# USB3-HUB.net
KiCad netlist of a schematic drawn in Altium Designer
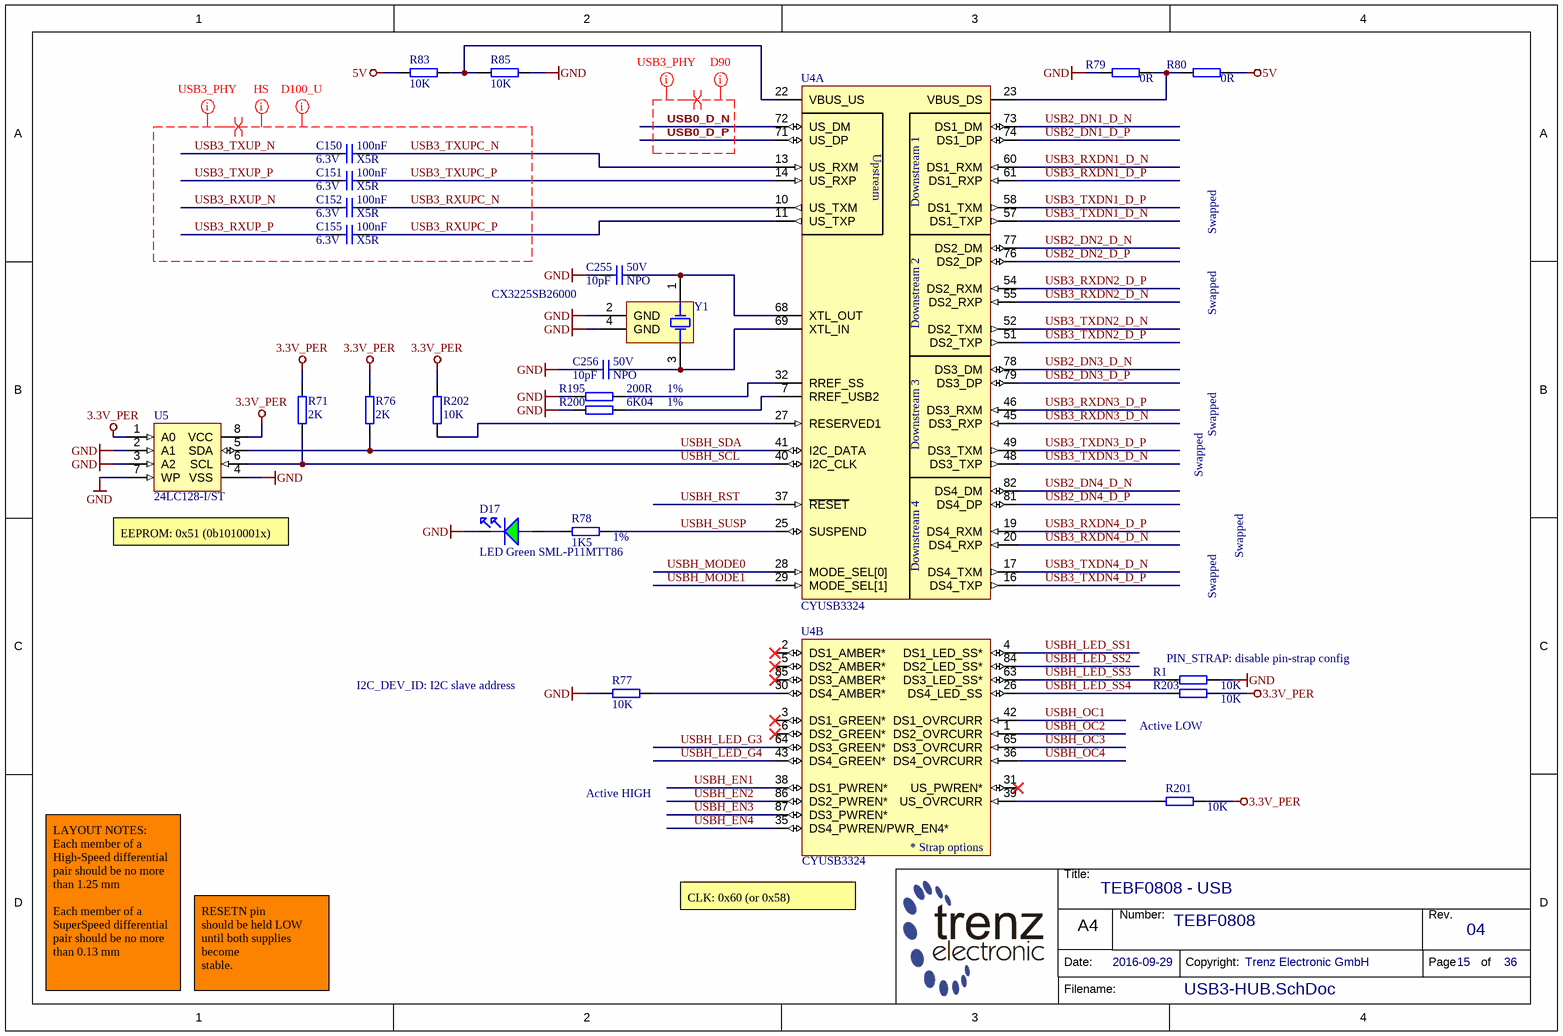
[diagram p0: USB3-HUB.SchDoc]

(export (version "E")
  (design (tool "Eeschema 10.0.6"))
  (components
    (comp (ref "C150")
      (value "100nF")
      (footprint "CAPC0603X33N")
      (description "KON 100nF 6.3V X5R SMD 10%")
      (fields
        (field (name "VOLTAGE") "6.3V")
        (field (name "TECHNOLOGY") "X5R")
        (field (name "TOLERANCE") "10%")
      )
      (libsource (lib "TE") (part "CAP-NP"))
    )
    (comp (ref "C151")
      (value "100nF")
      (footprint "CAPC0603X33N")
      (description "KON 100nF 6.3V X5R SMD 10%")
      (fields
        (field (name "VOLTAGE") "6.3V")
        (field (name "TECHNOLOGY") "X5R")
        (field (name "TOLERANCE") "10%")
      )
      (libsource (lib "TE") (part "CAP-NP"))
    )
    (comp (ref "C152")
      (value "100nF")
      (footprint "CAPC0603X33N")
      (description "KON 100nF 6.3V X5R SMD 10%")
      (fields
        (field (name "VOLTAGE") "6.3V")
        (field (name "TECHNOLOGY") "X5R")
        (field (name "TOLERANCE") "10%")
      )
      (libsource (lib "TE") (part "CAP-NP"))
    )
    (comp (ref "C155")
      (value "100nF")
      (footprint "CAPC0603X33N")
      (description "KON 100nF 6.3V X5R SMD 10%")
      (fields
        (field (name "VOLTAGE") "6.3V")
        (field (name "TECHNOLOGY") "X5R")
        (field (name "TOLERANCE") "10%")
      )
      (libsource (lib "TE") (part "CAP-NP"))
    )
    (comp (ref "C255")
      (value "10pF")
      (footprint "CAPC1005X55N")
      (description "KON 10pF NPO 50V SMD 5%")
      (fields
        (field (name "VOLTAGE") "50V")
        (field (name "TECHNOLOGY") "NPO")
        (field (name "TOLERANCE") "5%")
      )
      (libsource (lib "TE") (part "CAP-NP"))
    )
    (comp (ref "C256")
      (value "10pF")
      (footprint "CAPC1005X55N")
      (description "KON 10pF NPO 50V SMD 5%")
      (fields
        (field (name "VOLTAGE") "50V")
        (field (name "TECHNOLOGY") "NPO")
        (field (name "TOLERANCE") "5%")
      )
      (libsource (lib "TE") (part "CAP-NP"))
    )
    (comp (ref "D17")
      (value "LED Green SML-P11MTT86")
      (footprint "LEDC1006X25N_GREEN")
      (description "LED Grün SML-P11MTT86 SMD")
      (libsource (lib "TE") (part "LED_GRUEN"))
    )
    (comp (ref "R1")
      (value "10K")
      (footprint "RESC1005X40N")
      (description "WID SMD 10K 1% 0,063W")
      (fields (field (name "TOLERANCE") "1%"))
      (libsource (lib "TE") (part "RES"))
    )
    (comp (ref "R71")
      (value "2K")
      (footprint "RESC1005X40N")
      (description "WID SMD 2K 1% 0,063W")
      (fields (field (name "TOLERANCE") "1%"))
      (libsource (lib "TE") (part "RES"))
    )
    (comp (ref "R76")
      (value "2K")
      (footprint "RESC1005X40N")
      (description "WID SMD 2K 1% 0,063W")
      (fields (field (name "TOLERANCE") "1%"))
      (libsource (lib "TE") (part "RES"))
    )
    (comp (ref "R77")
      (value "10K")
      (footprint "RESC1005X40N")
      (description "WID SMD 10K 1% 0,063W")
      (fields (field (name "TOLERANCE") "1%"))
      (libsource (lib "TE") (part "RES"))
    )
    (comp (ref "R78")
      (value "1K5")
      (footprint "RESC1005X40N")
      (description "WID SMD 1K5 1% 0,063W")
      (fields (field (name "TOLERANCE") "1%"))
      (libsource (lib "TE") (part "RES"))
    )
    (comp (ref "R79")
      (value "0R")
      (footprint "RESC1005X40N")
      (description "WID SMD 0R")
      (fields (field (name "TOLERANCE") "1%"))
      (libsource (lib "TE") (part "RES"))
    )
    (comp (ref "R80")
      (value "0R")
      (footprint "RESC1005X40N")
      (description "WID SMD 0R")
      (fields (field (name "TOLERANCE") "1%"))
      (libsource (lib "TE") (part "RES"))
    )
    (comp (ref "R83")
      (value "10K")
      (footprint "RESC1005X40N")
      (description "WID SMD 10K 1% 0,063W")
      (fields (field (name "TOLERANCE") "1%"))
      (libsource (lib "TE") (part "RES"))
    )
    (comp (ref "R85")
      (value "10K")
      (footprint "RESC1005X40N")
      (description "WID SMD 10K 1% 0,063W")
      (fields (field (name "TOLERANCE") "1%"))
      (libsource (lib "TE") (part "RES"))
    )
    (comp (ref "R195")
      (value "200R")
      (footprint "RESC1005X40N")
      (description "WID SMD 200R 1% 0,063W")
      (fields (field (name "TOLERANCE") "1%"))
      (libsource (lib "TE") (part "RES"))
    )
    (comp (ref "R200")
      (value "6K04")
      (footprint "RESC1005X40N")
      (description "WID SMD 6K04 1% 0,063W")
      (fields (field (name "TOLERANCE") "1%"))
      (libsource (lib "TE") (part "RES"))
    )
    (comp (ref "R201")
      (value "10K")
      (footprint "RESC1005X40N")
      (description "WID SMD 10K 1% 0,063W")
      (fields (field (name "TOLERANCE") "1%"))
      (libsource (lib "TE") (part "RES"))
    )
    (comp (ref "R202")
      (value "10K")
      (footprint "RESC1005X40N")
      (description "WID SMD 10K 1% 0,063W")
      (fields (field (name "TOLERANCE") "1%"))
      (libsource (lib "TE") (part "RES"))
    )
    (comp (ref "R203")
      (value "10K")
      (footprint "RESC1005X40N")
      (description "WID SMD 10K 1% 0,063W")
      (fields (field (name "TOLERANCE") "1%"))
      (libsource (lib "TE") (part "RES"))
    )
    (comp (ref "U4")
      (value "CYUSB3324")
      (footprint "QFN40P10X10X1-89T530")
      (description "CYUSB3324-88LTXC USB 3.0 Hub")
      (libsource (lib "TE") (part "CYUSB3324"))
    )
    (comp (ref "U5")
      (value "24LC128-I/ST")
      (footprint "SOP65P640X120-8N-MC")
      (libsource (lib "TE") (part "24LC128I"))
    )
    (comp (ref "Y1")
      (value "CX3225SB26000")
      (footprint "OSCCC320X250X60N")
      (description "Quarz Crystal 26Mhz 10ppm 8pF -20C +70°C")
      (libsource (lib "TE") (part "ABM8G"))
    )
  )
  (nets
    (net (code "1") (name "/USB0_D_N") (class "Default")
      (node (ref "U4") (pin "72") (pinfunction "US_DM_72") (pintype "bidirectional"))
    )
    (net (code "2") (name "/USB0_D_P") (class "Default")
      (node (ref "U4") (pin "71") (pinfunction "US_DP_71") (pintype "bidirectional"))
    )
    (net (code "3") (name "/USB2_DN1_D_N") (class "Default")
      (node (ref "U4") (pin "73") (pinfunction "DS1_DM_73") (pintype "bidirectional"))
    )
    (net (code "4") (name "/USB2_DN1_D_P") (class "Default")
      (node (ref "U4") (pin "74") (pinfunction "DS1_DP_74") (pintype "bidirectional"))
    )
    (net (code "5") (name "/USB2_DN2_D_N") (class "Default")
      (node (ref "U4") (pin "77") (pinfunction "DS2_DM_77") (pintype "bidirectional"))
    )
    (net (code "6") (name "/USB2_DN2_D_P") (class "Default")
      (node (ref "U4") (pin "76") (pinfunction "DS2_DP_76") (pintype "bidirectional"))
    )
    (net (code "7") (name "/USB2_DN3_D_N") (class "Default")
      (node (ref "U4") (pin "78") (pinfunction "DS3_DM_78") (pintype "bidirectional"))
    )
    (net (code "8") (name "/USB2_DN3_D_P") (class "Default")
      (node (ref "U4") (pin "79") (pinfunction "DS3_DP_79") (pintype "bidirectional"))
    )
    (net (code "9") (name "/USB2_DN4_D_N") (class "Default")
      (node (ref "U4") (pin "82") (pinfunction "DS4_DM_82") (pintype "bidirectional"))
    )
    (net (code "10") (name "/USB2_DN4_D_P") (class "Default")
      (node (ref "U4") (pin "81") (pinfunction "DS4_DP_81") (pintype "bidirectional"))
    )
    (net (code "11") (name "/USB3_RXDN1_D_N") (class "Default")
      (node (ref "U4") (pin "60") (pinfunction "DS1_RXM_60") (pintype "input"))
    )
    (net (code "12") (name "/USB3_RXDN1_D_P") (class "Default")
      (node (ref "U4") (pin "61") (pinfunction "DS1_RXP_61") (pintype "input"))
    )
    (net (code "13") (name "/USB3_RXDN2_D_N") (class "Default")
      (node (ref "U4") (pin "55") (pinfunction "DS2_RXP_55") (pintype "input"))
    )
    (net (code "14") (name "/USB3_RXDN2_D_P") (class "Default")
      (node (ref "U4") (pin "54") (pinfunction "DS2_RXM_54") (pintype "input"))
    )
    (net (code "15") (name "/USB3_RXDN3_D_N") (class "Default")
      (node (ref "U4") (pin "45") (pinfunction "DS3_RXP_45") (pintype "input"))
    )
    (net (code "16") (name "/USB3_RXDN3_D_P") (class "Default")
      (node (ref "U4") (pin "46") (pinfunction "DS3_RXM_46") (pintype "input"))
    )
    (net (code "17") (name "/USB3_RXDN4_D_N") (class "Default")
      (node (ref "U4") (pin "20") (pinfunction "DS4_RXP_20") (pintype "input"))
    )
    (net (code "18") (name "/USB3_RXDN4_D_P") (class "Default")
      (node (ref "U4") (pin "19") (pinfunction "DS4_RXM_19") (pintype "input"))
    )
    (net (code "19") (name "/USB3_RXUPC_N") (class "Default")
      (node (ref "C152") (pin "2") (pinfunction "2_2") (pintype "passive"))
      (node (ref "U4") (pin "10") (pinfunction "US_TXM_10") (pintype "output"))
    )
    (net (code "20") (name "/USB3_RXUPC_P") (class "Default")
      (node (ref "C155") (pin "2") (pinfunction "2_2") (pintype "passive"))
      (node (ref "U4") (pin "11") (pinfunction "US_TXP_11") (pintype "output"))
    )
    (net (code "21") (name "/USB3_RXUP_N") (class "Default")
      (node (ref "C152") (pin "1") (pinfunction "1_1") (pintype "passive"))
    )
    (net (code "22") (name "/USB3_RXUP_P") (class "Default")
      (node (ref "C155") (pin "1") (pinfunction "1_1") (pintype "passive"))
    )
    (net (code "23") (name "/USB3_TXDN1_D_N") (class "Default")
      (node (ref "U4") (pin "57") (pinfunction "DS1_TXP_57") (pintype "output"))
    )
    (net (code "24") (name "/USB3_TXDN1_D_P") (class "Default")
      (node (ref "U4") (pin "58") (pinfunction "DS1_TXM_58") (pintype "output"))
    )
    (net (code "25") (name "/USB3_TXDN2_D_N") (class "Default")
      (node (ref "U4") (pin "52") (pinfunction "DS2_TXM_52") (pintype "output"))
    )
    (net (code "26") (name "/USB3_TXDN2_D_P") (class "Default")
      (node (ref "U4") (pin "51") (pinfunction "DS2_TXP_51") (pintype "output"))
    )
    (net (code "27") (name "/USB3_TXDN3_D_N") (class "Default")
      (node (ref "U4") (pin "48") (pinfunction "DS3_TXP_48") (pintype "output"))
    )
    (net (code "28") (name "/USB3_TXDN3_D_P") (class "Default")
      (node (ref "U4") (pin "49") (pinfunction "DS3_TXM_49") (pintype "output"))
    )
    (net (code "29") (name "/USB3_TXDN4_D_N") (class "Default")
      (node (ref "U4") (pin "17") (pinfunction "DS4_TXM_17") (pintype "output"))
    )
    (net (code "30") (name "/USB3_TXDN4_D_P") (class "Default")
      (node (ref "U4") (pin "16") (pinfunction "DS4_TXP_16") (pintype "output"))
    )
    (net (code "31") (name "/USB3_TXUPC_N") (class "Default")
      (node (ref "C150") (pin "2") (pinfunction "2_2") (pintype "passive"))
      (node (ref "U4") (pin "13") (pinfunction "US_RXM_13") (pintype "input"))
    )
    (net (code "32") (name "/USB3_TXUPC_P") (class "Default")
      (node (ref "C151") (pin "2") (pinfunction "2_2") (pintype "passive"))
      (node (ref "U4") (pin "14") (pinfunction "US_RXP_14") (pintype "input"))
    )
    (net (code "33") (name "/USB3_TXUP_N") (class "Default")
      (node (ref "C150") (pin "1") (pinfunction "1_1") (pintype "passive"))
    )
    (net (code "34") (name "/USB3_TXUP_P") (class "Default")
      (node (ref "C151") (pin "1") (pinfunction "1_1") (pintype "passive"))
    )
    (net (code "35") (name "/USBH_EN1") (class "Default")
      (node (ref "U4") (pin "38") (pinfunction "DS1_PWREN*_38") (pintype "bidirectional"))
    )
    (net (code "36") (name "/USBH_EN2") (class "Default")
      (node (ref "U4") (pin "86") (pinfunction "DS2_PWREN*_86") (pintype "bidirectional"))
    )
    (net (code "37") (name "/USBH_EN3") (class "Default")
      (node (ref "U4") (pin "87") (pinfunction "DS3_PWREN*_87") (pintype "bidirectional"))
    )
    (net (code "38") (name "/USBH_EN4") (class "Default")
      (node (ref "U4") (pin "35") (pinfunction "DS4_PWREN/PWR_EN4*_35") (pintype "bidirectional"))
    )
    (net (code "39") (name "/USBH_LED_G3") (class "Default")
      (node (ref "U4") (pin "64") (pinfunction "DS3_GREEN*_64") (pintype "bidirectional"))
    )
    (net (code "40") (name "/USBH_LED_G4") (class "Default")
      (node (ref "U4") (pin "43") (pinfunction "DS4_GREEN*_43") (pintype "bidirectional"))
    )
    (net (code "41") (name "/USBH_LED_SS1") (class "Default")
      (node (ref "U4") (pin "4") (pinfunction "DS1_LED_SS*_4") (pintype "bidirectional"))
    )
    (net (code "42") (name "/USBH_LED_SS2") (class "Default")
      (node (ref "U4") (pin "84") (pinfunction "DS2_LED_SS*_84") (pintype "bidirectional"))
    )
    (net (code "43") (name "/USBH_LED_SS3") (class "Default")
      (node (ref "R1") (pin "2") (pinfunction "2_2") (pintype "passive"))
      (node (ref "U4") (pin "63") (pinfunction "DS3_LED_SS*_63") (pintype "bidirectional"))
    )
    (net (code "44") (name "/USBH_LED_SS4") (class "Default")
      (node (ref "R203") (pin "2") (pinfunction "2_2") (pintype "passive"))
      (node (ref "U4") (pin "26") (pinfunction "DS4_LED_SS_26") (pintype "bidirectional"))
    )
    (net (code "45") (name "/USBH_MODE0") (class "Default")
      (node (ref "U4") (pin "28") (pinfunction "MODE_SEL[0]_28") (pintype "input"))
    )
    (net (code "46") (name "/USBH_MODE1") (class "Default")
      (node (ref "U4") (pin "29") (pinfunction "MODE_SEL[1]_29") (pintype "input"))
    )
    (net (code "47") (name "/USBH_OC1") (class "Default")
      (node (ref "U4") (pin "42") (pinfunction "DS1_OVRCURR_42") (pintype "input"))
    )
    (net (code "48") (name "/USBH_OC2") (class "Default")
      (node (ref "U4") (pin "1") (pinfunction "DS2_OVRCURR_1") (pintype "input"))
    )
    (net (code "49") (name "/USBH_OC3") (class "Default")
      (node (ref "U4") (pin "65") (pinfunction "DS3_OVRCURR_65") (pintype "input"))
    )
    (net (code "50") (name "/USBH_OC4") (class "Default")
      (node (ref "U4") (pin "36") (pinfunction "DS4_OVRCURR_36") (pintype "input"))
    )
    (net (code "51") (name "/USBH_RST") (class "Default")
      (node (ref "U4") (pin "37") (pinfunction "~{RESET}_37") (pintype "input"))
    )
    (net (code "52") (name "/USBH_SCL") (class "Default")
      (node (ref "R71") (pin "1") (pinfunction "1_1") (pintype "passive"))
      (node (ref "U4") (pin "40") (pinfunction "I2C_CLK_40") (pintype "bidirectional"))
      (node (ref "U5") (pin "6") (pinfunction "SCL_6") (pintype "input"))
    )
    (net (code "53") (name "/USBH_SDA") (class "Default")
      (node (ref "R76") (pin "1") (pinfunction "1_1") (pintype "passive"))
      (node (ref "U4") (pin "41") (pinfunction "I2C_DATA_41") (pintype "bidirectional"))
      (node (ref "U5") (pin "5") (pinfunction "SDA_5") (pintype "bidirectional"))
    )
    (net (code "54") (name "/USBH_SUSP") (class "Default")
      (node (ref "R78") (pin "1") (pinfunction "1_1") (pintype "passive"))
      (node (ref "U4") (pin "25") (pinfunction "SUSPEND_25") (pintype "bidirectional"))
    )
    (net (code "55") (name "3.3V_PER") (class "Default")
      (node (ref "R201") (pin "1") (pinfunction "1_1") (pintype "passive"))
      (node (ref "R202") (pin "1") (pinfunction "1_1") (pintype "passive"))
      (node (ref "R203") (pin "1") (pinfunction "1_1") (pintype "passive"))
      (node (ref "R71") (pin "2") (pinfunction "2_2") (pintype "passive"))
      (node (ref "R76") (pin "2") (pinfunction "2_2") (pintype "passive"))
      (node (ref "U5") (pin "1") (pinfunction "A0_1") (pintype "input"))
      (node (ref "U5") (pin "8") (pinfunction "VCC_8") (pintype "power_in"))
    )
    (net (code "56") (name "5V") (class "Default")
      (node (ref "R80") (pin "1") (pinfunction "1_1") (pintype "passive"))
      (node (ref "R83") (pin "2") (pinfunction "2_2") (pintype "passive"))
    )
    (net (code "57") (name "GND") (class "Default")
      (node (ref "C255") (pin "1") (pinfunction "1_1") (pintype "passive"))
      (node (ref "C256") (pin "1") (pinfunction "1_1") (pintype "passive"))
      (node (ref "D17") (pin "K") (pinfunction "K_K") (pintype "passive"))
      (node (ref "R1") (pin "1") (pinfunction "1_1") (pintype "passive"))
      (node (ref "R195") (pin "1") (pinfunction "1_1") (pintype "passive"))
      (node (ref "R200") (pin "1") (pinfunction "1_1") (pintype "passive"))
      (node (ref "R77") (pin "1") (pinfunction "1_1") (pintype "passive"))
      (node (ref "R79") (pin "2") (pinfunction "2_2") (pintype "passive"))
      (node (ref "R85") (pin "1") (pinfunction "1_1") (pintype "passive"))
      (node (ref "U5") (pin "2") (pinfunction "A1_2") (pintype "input"))
      (node (ref "U5") (pin "3") (pinfunction "A2_3") (pintype "input"))
      (node (ref "U5") (pin "4") (pinfunction "VSS_4") (pintype "power_in"))
      (node (ref "U5") (pin "7") (pinfunction "WP_7") (pintype "input"))
      (node (ref "Y1") (pin "2") (pinfunction "GND_2") (pintype "passive"))
      (node (ref "Y1") (pin "4") (pinfunction "GND_4") (pintype "passive"))
    )
    (net (code "58") (name "Net-(D17-PadA)") (class "Default")
      (node (ref "D17") (pin "A") (pinfunction "A_A") (pintype "passive"))
      (node (ref "R78") (pin "2") (pinfunction "2_2") (pintype "passive"))
    )
    (net (code "59") (name "Net-(U4A-RESERVED1)") (class "Default")
      (node (ref "R202") (pin "2") (pinfunction "2_2") (pintype "passive"))
      (node (ref "U4") (pin "27") (pinfunction "RESERVED1_27") (pintype "input"))
    )
    (net (code "60") (name "Net-(U4A-RREF_SS)") (class "Default")
      (node (ref "R195") (pin "2") (pinfunction "2_2") (pintype "passive"))
      (node (ref "U4") (pin "32") (pinfunction "RREF_SS_32") (pintype "passive"))
    )
    (net (code "61") (name "Net-(U4A-RREF_USB2)") (class "Default")
      (node (ref "R200") (pin "2") (pinfunction "2_2") (pintype "passive"))
      (node (ref "U4") (pin "7") (pinfunction "RREF_USB2_7") (pintype "passive"))
    )
    (net (code "62") (name "Net-(U4A-VBUS_DS)") (class "Default")
      (node (ref "R79") (pin "1") (pinfunction "1_1") (pintype "passive"))
      (node (ref "R80") (pin "2") (pinfunction "2_2") (pintype "passive"))
      (node (ref "U4") (pin "23") (pinfunction "VBUS_DS_23") (pintype "power_in"))
    )
    (net (code "63") (name "Net-(U4A-VBUS_US)") (class "Default")
      (node (ref "R83") (pin "1") (pinfunction "1_1") (pintype "passive"))
      (node (ref "R85") (pin "2") (pinfunction "2_2") (pintype "passive"))
      (node (ref "U4") (pin "22") (pinfunction "VBUS_US_22") (pintype "power_in"))
    )
    (net (code "64") (name "Net-(U4A-XTL_IN)") (class "Default")
      (node (ref "C256") (pin "2") (pinfunction "2_2") (pintype "passive"))
      (node (ref "U4") (pin "69") (pinfunction "XTL_IN_69") (pintype "passive"))
      (node (ref "Y1") (pin "3") (pinfunction "OSC2_3") (pintype "passive"))
    )
    (net (code "65") (name "Net-(U4A-XTL_OUT)") (class "Default")
      (node (ref "C255") (pin "2") (pinfunction "2_2") (pintype "passive"))
      (node (ref "U4") (pin "68") (pinfunction "XTL_OUT_68") (pintype "passive"))
      (node (ref "Y1") (pin "1") (pinfunction "OSC1_1") (pintype "passive"))
    )
    (net (code "66") (name "Net-(U4B-DS4_AMBER*)") (class "Default")
      (node (ref "R77") (pin "2") (pinfunction "2_2") (pintype "passive"))
      (node (ref "U4") (pin "30") (pinfunction "DS4_AMBER*_30") (pintype "bidirectional"))
    )
    (net (code "67") (name "Net-(U4B-US_OVRCURR)") (class "Default")
      (node (ref "R201") (pin "2") (pinfunction "2_2") (pintype "passive"))
      (node (ref "U4") (pin "39") (pinfunction "US_OVRCURR_39") (pintype "input"))
    )
    (net (code "68") (name "unconnected-(U4B-DS1_AMBER*-Pad2)") (class "Default")
      (node (ref "U4") (pin "2") (pinfunction "DS1_AMBER*_2") (pintype "bidirectional+no_connect"))
    )
    (net (code "69") (name "unconnected-(U4B-DS1_GREEN*-Pad3)") (class "Default")
      (node (ref "U4") (pin "3") (pinfunction "DS1_GREEN*_3") (pintype "bidirectional+no_connect"))
    )
    (net (code "70") (name "unconnected-(U4B-DS2_AMBER*-Pad5)") (class "Default")
      (node (ref "U4") (pin "5") (pinfunction "DS2_AMBER*_5") (pintype "bidirectional+no_connect"))
    )
    (net (code "71") (name "unconnected-(U4B-DS2_GREEN*-Pad6)") (class "Default")
      (node (ref "U4") (pin "6") (pinfunction "DS2_GREEN*_6") (pintype "bidirectional+no_connect"))
    )
    (net (code "72") (name "unconnected-(U4B-DS3_AMBER*-Pad85)") (class "Default")
      (node (ref "U4") (pin "85") (pinfunction "DS3_AMBER*_85") (pintype "bidirectional+no_connect"))
    )
    (net (code "73") (name "unconnected-(U4B-US_PWREN*-Pad31)") (class "Default")
      (node (ref "U4") (pin "31") (pinfunction "US_PWREN*_31") (pintype "bidirectional+no_connect"))
    )
  )
)
